# TF-CARD.net
KiCad netlist of a schematic drawn in Altium Designer
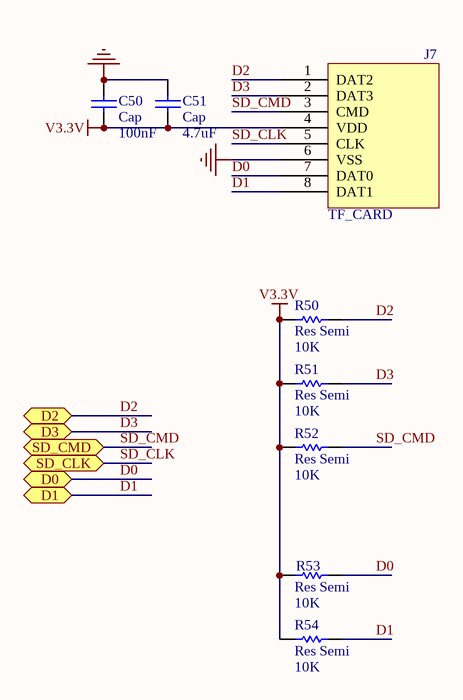
[diagram p0: TF-CARD.SchDoc]

(export (version "E")
  (design (tool "Eeschema 10.0.6"))
  (components
    (comp (ref "C50")
      (value "Cap")
      (footprint "R0603N")
      (description "Capacitor")
      (fields (field (name "ALTIUM_VALUE") "100nF") (field (name "PUBLISHER") "Altium Limited"))
      (libsource (lib "Miscellaneous Devices") (part "Cap"))
    )
    (comp (ref "C51")
      (value "Cap")
      (footprint "R0603N")
      (description "Capacitor")
      (fields (field (name "ALTIUM_VALUE") "4.7uF") (field (name "PUBLISHER") "Altium Limited"))
      (libsource (lib "Miscellaneous Devices") (part "Cap"))
    )
    (comp (ref "J7") (value "TF_CARD") (footprint "TFP09-2-12B") (libsource (lib "*") (part "Component_1")))
    (comp (ref "R50")
      (value "Res Semi")
      (footprint "R0603N")
      (description "Semiconductor Resistor")
      (fields (field (name "ALTIUM_VALUE") "10K") (field (name "PUBLISHER") "Altium Limited"))
      (libsource (lib "Miscellaneous Devices") (part "Res Semi"))
    )
    (comp (ref "R51")
      (value "Res Semi")
      (footprint "R0603N")
      (description "Semiconductor Resistor")
      (fields (field (name "ALTIUM_VALUE") "10K") (field (name "PUBLISHER") "Altium Limited"))
      (libsource (lib "Miscellaneous Devices") (part "Res Semi"))
    )
    (comp (ref "R52")
      (value "Res Semi")
      (footprint "R0603N")
      (description "Semiconductor Resistor")
      (fields (field (name "ALTIUM_VALUE") "10K") (field (name "PUBLISHER") "Altium Limited"))
      (libsource (lib "Miscellaneous Devices") (part "Res Semi"))
    )
    (comp (ref "R53")
      (value "Res Semi")
      (footprint "R0603N")
      (description "Semiconductor Resistor")
      (fields (field (name "ALTIUM_VALUE") "10K") (field (name "PUBLISHER") "Altium Limited"))
      (libsource (lib "Miscellaneous Devices") (part "Res Semi"))
    )
    (comp (ref "R54")
      (value "Res Semi")
      (footprint "r0603N")
      (description "Semiconductor Resistor")
      (fields (field (name "ALTIUM_VALUE") "10K") (field (name "PUBLISHER") "Altium Limited"))
      (libsource (lib "Miscellaneous Devices") (part "Res Semi"))
    )
  )
  (nets
    (net (code "1") (name "/D0") (class "Default")
      (node (ref "J7") (pin "7") (pinfunction "DAT0_7") (pintype "passive"))
      (node (ref "R53") (pin "2") (pinfunction "2_2") (pintype "passive"))
    )
    (net (code "2") (name "/D1") (class "Default")
      (node (ref "J7") (pin "8") (pinfunction "DAT1_8") (pintype "passive"))
      (node (ref "R54") (pin "2") (pinfunction "2_2") (pintype "passive"))
    )
    (net (code "3") (name "/D2") (class "Default")
      (node (ref "J7") (pin "1") (pinfunction "DAT2_1") (pintype "passive"))
      (node (ref "R50") (pin "2") (pinfunction "2_2") (pintype "passive"))
    )
    (net (code "4") (name "/D3") (class "Default")
      (node (ref "J7") (pin "2") (pinfunction "DAT3_2") (pintype "passive"))
      (node (ref "R51") (pin "2") (pinfunction "2_2") (pintype "passive"))
    )
    (net (code "5") (name "/SD_CLK") (class "Default")
      (node (ref "J7") (pin "5") (pinfunction "CLK_5") (pintype "passive"))
    )
    (net (code "6") (name "/SD_CMD") (class "Default")
      (node (ref "J7") (pin "3") (pinfunction "CMD_3") (pintype "passive"))
      (node (ref "R52") (pin "2") (pinfunction "2_2") (pintype "passive"))
    )
    (net (code "7") (name "GND") (class "Default")
      (node (ref "C50") (pin "2") (pinfunction "2_2") (pintype "passive"))
      (node (ref "C51") (pin "2") (pinfunction "2_2") (pintype "passive"))
      (node (ref "J7") (pin "6") (pinfunction "VSS_6") (pintype "passive"))
    )
    (net (code "8") (name "V3.3V") (class "Default")
      (node (ref "C50") (pin "1") (pinfunction "1_1") (pintype "passive"))
      (node (ref "C51") (pin "1") (pinfunction "1_1") (pintype "passive"))
      (node (ref "J7") (pin "4") (pinfunction "VDD_4") (pintype "passive"))
      (node (ref "R50") (pin "1") (pinfunction "1_1") (pintype "passive"))
      (node (ref "R51") (pin "1") (pinfunction "1_1") (pintype "passive"))
      (node (ref "R52") (pin "1") (pinfunction "1_1") (pintype "passive"))
      (node (ref "R53") (pin "1") (pinfunction "1_1") (pintype "passive"))
      (node (ref "R54") (pin "1") (pinfunction "1_1") (pintype "passive"))
    )
  )
)
